# Plantersens_Soil_Sensor.net
KiCad netlist of a schematic drawn in EAGLE
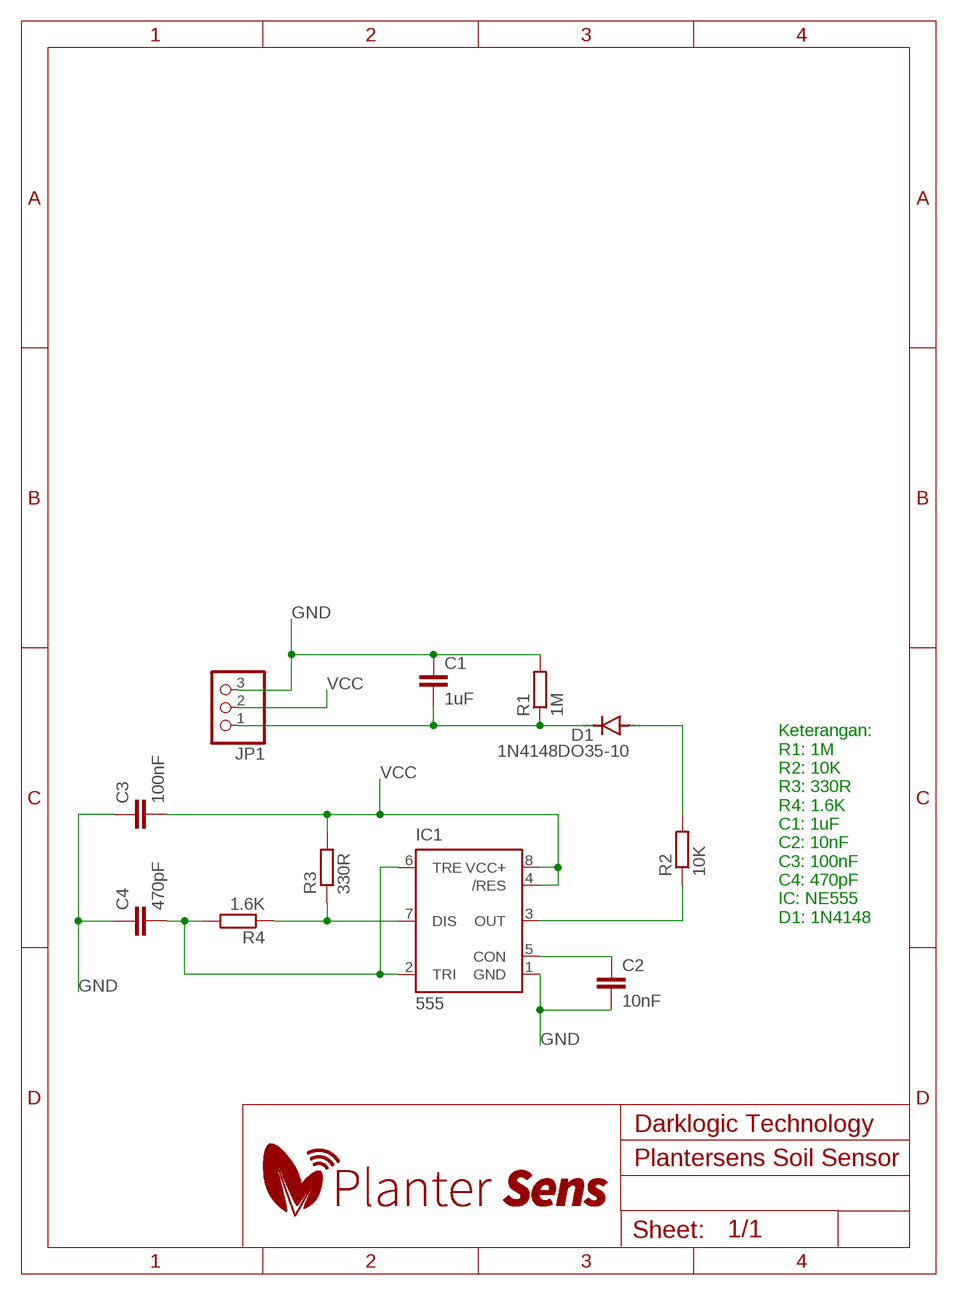
[diagram p0: schematic, sheet 1]

(export (version "E")
  (design (tool "Eeschema 10.0.6"))
  (components
    (comp (ref "C1")
      (value "1uF")
      (footprint "eagle-import:C2.5-2")
      (libsource (lib "eagle-import") (part "C2.5/2"))
    )
    (comp (ref "C2")
      (value "10nF")
      (footprint "eagle-import:C2.5-2")
      (libsource (lib "eagle-import") (part "C2.5/2"))
    )
    (comp (ref "C3")
      (value "100nF")
      (footprint "eagle-import:C2.5-2")
      (libsource (lib "eagle-import") (part "C2.5/2"))
    )
    (comp (ref "C4")
      (value "470pF")
      (footprint "eagle-import:C2.5-2")
      (libsource (lib "eagle-import") (part "C2.5/2"))
    )
    (comp (ref "D1")
      (value "1N4148DO35-10")
      (footprint "eagle-import:DO35-10")
      (libsource (lib "eagle-import") (part "1N4148DO35-10"))
    )
    (comp (ref "IC1")
      (value "555")
      (footprint "eagle-import:DIP08-KIT")
      (libsource (lib "eagle-import") (part "555KIT"))
    )
    (comp (ref "JP1")
      (value "PINHD-1X3")
      (footprint "eagle-import:1X03")
      (libsource (lib "eagle-import") (part "PINHD-1X3"))
    )
    (comp (ref "R1")
      (value "1M")
      (footprint "eagle-import:0207_10")
      (libsource (lib "eagle-import") (part "R-EU_0207/10"))
    )
    (comp (ref "R2")
      (value "10K")
      (footprint "eagle-import:0207_10")
      (libsource (lib "eagle-import") (part "R-EU_0207/10"))
    )
    (comp (ref "R3")
      (value "330R")
      (footprint "eagle-import:0207_10")
      (libsource (lib "eagle-import") (part "R-EU_0207/10"))
    )
    (comp (ref "R4")
      (value "1.6K")
      (footprint "eagle-import:0207_10")
      (libsource (lib "eagle-import") (part "R-EU_0207/10"))
    )
  )
  (nets
    (net (code "1") (name "/GND") (class "Default")
      (node (ref "C1") (pin "1") (pinfunction "1_1") (pintype "passive"))
      (node (ref "C2") (pin "2") (pinfunction "2_2") (pintype "passive"))
      (node (ref "C3") (pin "1") (pinfunction "1_1") (pintype "passive"))
      (node (ref "C4") (pin "1") (pinfunction "1_1") (pintype "passive"))
      (node (ref "IC1") (pin "1") (pinfunction "GND_1") (pintype "power_in"))
      (node (ref "JP1") (pin "3") (pinfunction "3_3") (pintype "passive"))
      (node (ref "R1") (pin "2") (pinfunction "2_2") (pintype "passive"))
    )
    (net (code "2") (name "/VCC") (class "Default")
      (node (ref "C3") (pin "2") (pinfunction "2_2") (pintype "passive"))
      (node (ref "IC1") (pin "4") (pinfunction "/RES_4") (pintype "input"))
      (node (ref "IC1") (pin "8") (pinfunction "VCC+_8") (pintype "power_in"))
      (node (ref "JP1") (pin "2") (pinfunction "2_2") (pintype "passive"))
      (node (ref "R3") (pin "2") (pinfunction "2_2") (pintype "passive"))
    )
    (net (code "3") (name "Net-(C1-Pad2)") (class "Default")
      (node (ref "C1") (pin "2") (pinfunction "2_2") (pintype "passive"))
      (node (ref "D1") (pin "C") (pinfunction "C_C") (pintype "passive"))
      (node (ref "JP1") (pin "1") (pinfunction "1_1") (pintype "passive"))
      (node (ref "R1") (pin "1") (pinfunction "1_1") (pintype "passive"))
    )
    (net (code "4") (name "Net-(D1-PadA)") (class "Default")
      (node (ref "D1") (pin "A") (pinfunction "A_A") (pintype "passive"))
      (node (ref "R2") (pin "2") (pinfunction "2_2") (pintype "passive"))
    )
    (net (code "5") (name "Net-(IC1-CON)") (class "Default")
      (node (ref "C2") (pin "1") (pinfunction "1_1") (pintype "passive"))
      (node (ref "IC1") (pin "5") (pinfunction "CON_5") (pintype "input"))
    )
    (net (code "6") (name "Net-(IC1-DIS)") (class "Default")
      (node (ref "IC1") (pin "7") (pinfunction "DIS_7") (pintype "input"))
      (node (ref "R3") (pin "1") (pinfunction "1_1") (pintype "passive"))
      (node (ref "R4") (pin "1") (pinfunction "1_1") (pintype "passive"))
    )
    (net (code "7") (name "Net-(IC1-OUT)") (class "Default")
      (node (ref "IC1") (pin "3") (pinfunction "OUT_3") (pintype "output"))
      (node (ref "R2") (pin "1") (pinfunction "1_1") (pintype "passive"))
    )
    (net (code "8") (name "Net-(IC1-TRE)") (class "Default")
      (node (ref "C4") (pin "2") (pinfunction "2_2") (pintype "passive"))
      (node (ref "IC1") (pin "2") (pinfunction "TRI_2") (pintype "input"))
      (node (ref "IC1") (pin "6") (pinfunction "TRE_6") (pintype "input"))
      (node (ref "R4") (pin "2") (pinfunction "2_2") (pintype "passive"))
    )
  )
)
